# namur_pi-dock.net
KiCad netlist of a schematic drawn in Altium Designer
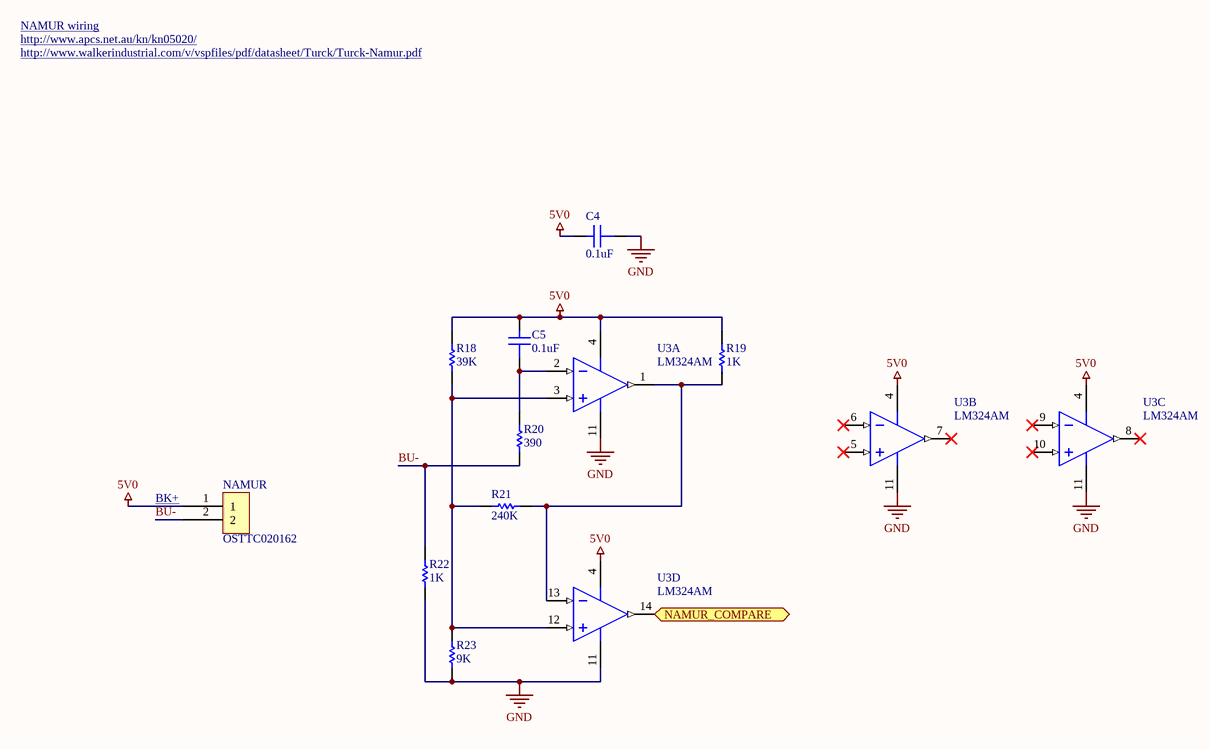
[diagram p0: namur_pi-dock.SchDoc]

(export (version "E")
  (design (tool "Eeschema 10.0.6"))
  (components
    (comp (ref "C4")
      (value "0.1uF")
      (footprint "CAP_8085")
      (description "SMD Chip Capacitor")
      (libsource (lib "[Asshat] Passives") (part "CHIP-CAP"))
    )
    (comp (ref "C5")
      (value "0.1uF")
      (footprint "CAP_8085")
      (description "SMD Chip Capacitor")
      (libsource (lib "[Asshat] Passives") (part "CHIP-CAP"))
    )
    (comp (ref "NAMUR")
      (value "OSTTC020162")
      (footprint "DIP2_5MM_SCREWTERM")
      (description "ON SHORE TERMINAL BLOCK 5MM VERT 2POS PCB")
      (libsource (lib "[Asshat] Connectors") (part "OSTTC020162"))
    )
    (comp (ref "R18")
      (value "39K")
      (footprint "RES_8085")
      (description "SMD Chip Resistor")
      (libsource (lib "[Asshat] Passives") (part "CHIP-RES"))
    )
    (comp (ref "R19")
      (value "1K")
      (footprint "RES_8085")
      (description "SMD Chip Resistor")
      (libsource (lib "[Asshat] Passives") (part "CHIP-RES"))
    )
    (comp (ref "R20")
      (value "390")
      (footprint "RES_8085")
      (description "SMD Chip Resistor")
      (libsource (lib "[Asshat] Passives") (part "CHIP-RES"))
    )
    (comp (ref "R21")
      (value "240K")
      (footprint "RES_8085")
      (description "SMD Chip Resistor")
      (libsource (lib "[Asshat] Passives") (part "CHIP-RES"))
    )
    (comp (ref "R22")
      (value "1K")
      (footprint "RES_8085")
      (description "SMD Chip Resistor")
      (libsource (lib "[Asshat] Passives") (part "CHIP-RES"))
    )
    (comp (ref "R23")
      (value "9K")
      (footprint "RES_8085")
      (description "SMD Chip Resistor")
      (libsource (lib "[Asshat] Passives") (part "CHIP-RES"))
    )
    (comp (ref "U3")
      (value "LM324AM")
      (footprint "M14A_N")
      (description "Low Power Quad Operational Amplifier, 14-pin Narrow SOIC")
      (fields
        (field (name "MANUFACTURER") "National Semiconductor")
        (field (name "PUBLISHER") "Altium Limited")
      )
      (libsource (lib "NSC Amplifier") (part "LM324AM"))
    )
  )
  (nets
    (net (code "1") (name "/BU-") (class "Default")
      (node (ref "NAMUR") (pin "2") (pinfunction "2_2") (pintype "passive"))
      (node (ref "R20") (pin "2") (pinfunction "2_2") (pintype "passive"))
      (node (ref "R22") (pin "1") (pinfunction "1_1") (pintype "passive"))
    )
    (net (code "2") (name "/NAMUR_COMPARE") (class "Default")
      (node (ref "U3") (pin "14") (pinfunction "OUT4_14") (pintype "output"))
    )
    (net (code "3") (name "5V0") (class "Default")
      (node (ref "C4") (pin "2") (pinfunction "2_2") (pintype "passive"))
      (node (ref "C5") (pin "2") (pinfunction "2_2") (pintype "passive"))
      (node (ref "NAMUR") (pin "1") (pinfunction "1_1") (pintype "passive"))
      (node (ref "R18") (pin "2") (pinfunction "2_2") (pintype "passive"))
      (node (ref "R19") (pin "2") (pinfunction "2_2") (pintype "passive"))
      (node (ref "U3") (pin "4") (pinfunction "V+_4") (pintype "power_in"))
    )
    (net (code "4") (name "GND") (class "Default")
      (node (ref "C4") (pin "1") (pinfunction "1_1") (pintype "passive"))
      (node (ref "R22") (pin "2") (pinfunction "2_2") (pintype "passive"))
      (node (ref "R23") (pin "1") (pinfunction "1_1") (pintype "passive"))
      (node (ref "U3") (pin "11") (pinfunction "GND_11") (pintype "power_in"))
    )
    (net (code "5") (name "Net-(U3A-IN1+)") (class "Default")
      (node (ref "R18") (pin "1") (pinfunction "1_1") (pintype "passive"))
      (node (ref "R21") (pin "1") (pinfunction "1_1") (pintype "passive"))
      (node (ref "R23") (pin "2") (pinfunction "2_2") (pintype "passive"))
      (node (ref "U3") (pin "12") (pinfunction "IN4+_12") (pintype "input"))
      (node (ref "U3") (pin "3") (pinfunction "IN1+_3") (pintype "input"))
    )
    (net (code "6") (name "Net-(U3A-IN1-)") (class "Default")
      (node (ref "C5") (pin "1") (pinfunction "1_1") (pintype "passive"))
      (node (ref "R20") (pin "1") (pinfunction "1_1") (pintype "passive"))
      (node (ref "U3") (pin "2") (pinfunction "IN1-_2") (pintype "input"))
    )
    (net (code "7") (name "Net-(U3A-OUT1)") (class "Default")
      (node (ref "R19") (pin "1") (pinfunction "1_1") (pintype "passive"))
      (node (ref "R21") (pin "2") (pinfunction "2_2") (pintype "passive"))
      (node (ref "U3") (pin "1") (pinfunction "OUT1_1") (pintype "output"))
      (node (ref "U3") (pin "13") (pinfunction "IN4-_13") (pintype "input"))
    )
    (net (code "8") (name "unconnected-(U3B-IN2+-Pad5)") (class "Default")
      (node (ref "U3") (pin "5") (pinfunction "IN2+_5") (pintype "input+no_connect"))
    )
    (net (code "9") (name "unconnected-(U3B-IN2--Pad6)") (class "Default")
      (node (ref "U3") (pin "6") (pinfunction "IN2-_6") (pintype "input+no_connect"))
    )
    (net (code "10") (name "unconnected-(U3B-OUT2-Pad7)") (class "Default")
      (node (ref "U3") (pin "7") (pinfunction "OUT2_7") (pintype "output+no_connect"))
    )
    (net (code "11") (name "unconnected-(U3C-IN3+-Pad10)") (class "Default")
      (node (ref "U3") (pin "10") (pinfunction "IN3+_10") (pintype "input+no_connect"))
    )
    (net (code "12") (name "unconnected-(U3C-IN3--Pad9)") (class "Default")
      (node (ref "U3") (pin "9") (pinfunction "IN3-_9") (pintype "input+no_connect"))
    )
    (net (code "13") (name "unconnected-(U3C-OUT3-Pad8)") (class "Default")
      (node (ref "U3") (pin "8") (pinfunction "OUT3_8") (pintype "output+no_connect"))
    )
  )
)
